# USB2XXX_1.net
KiCad netlist of a schematic drawn in Altium Designer
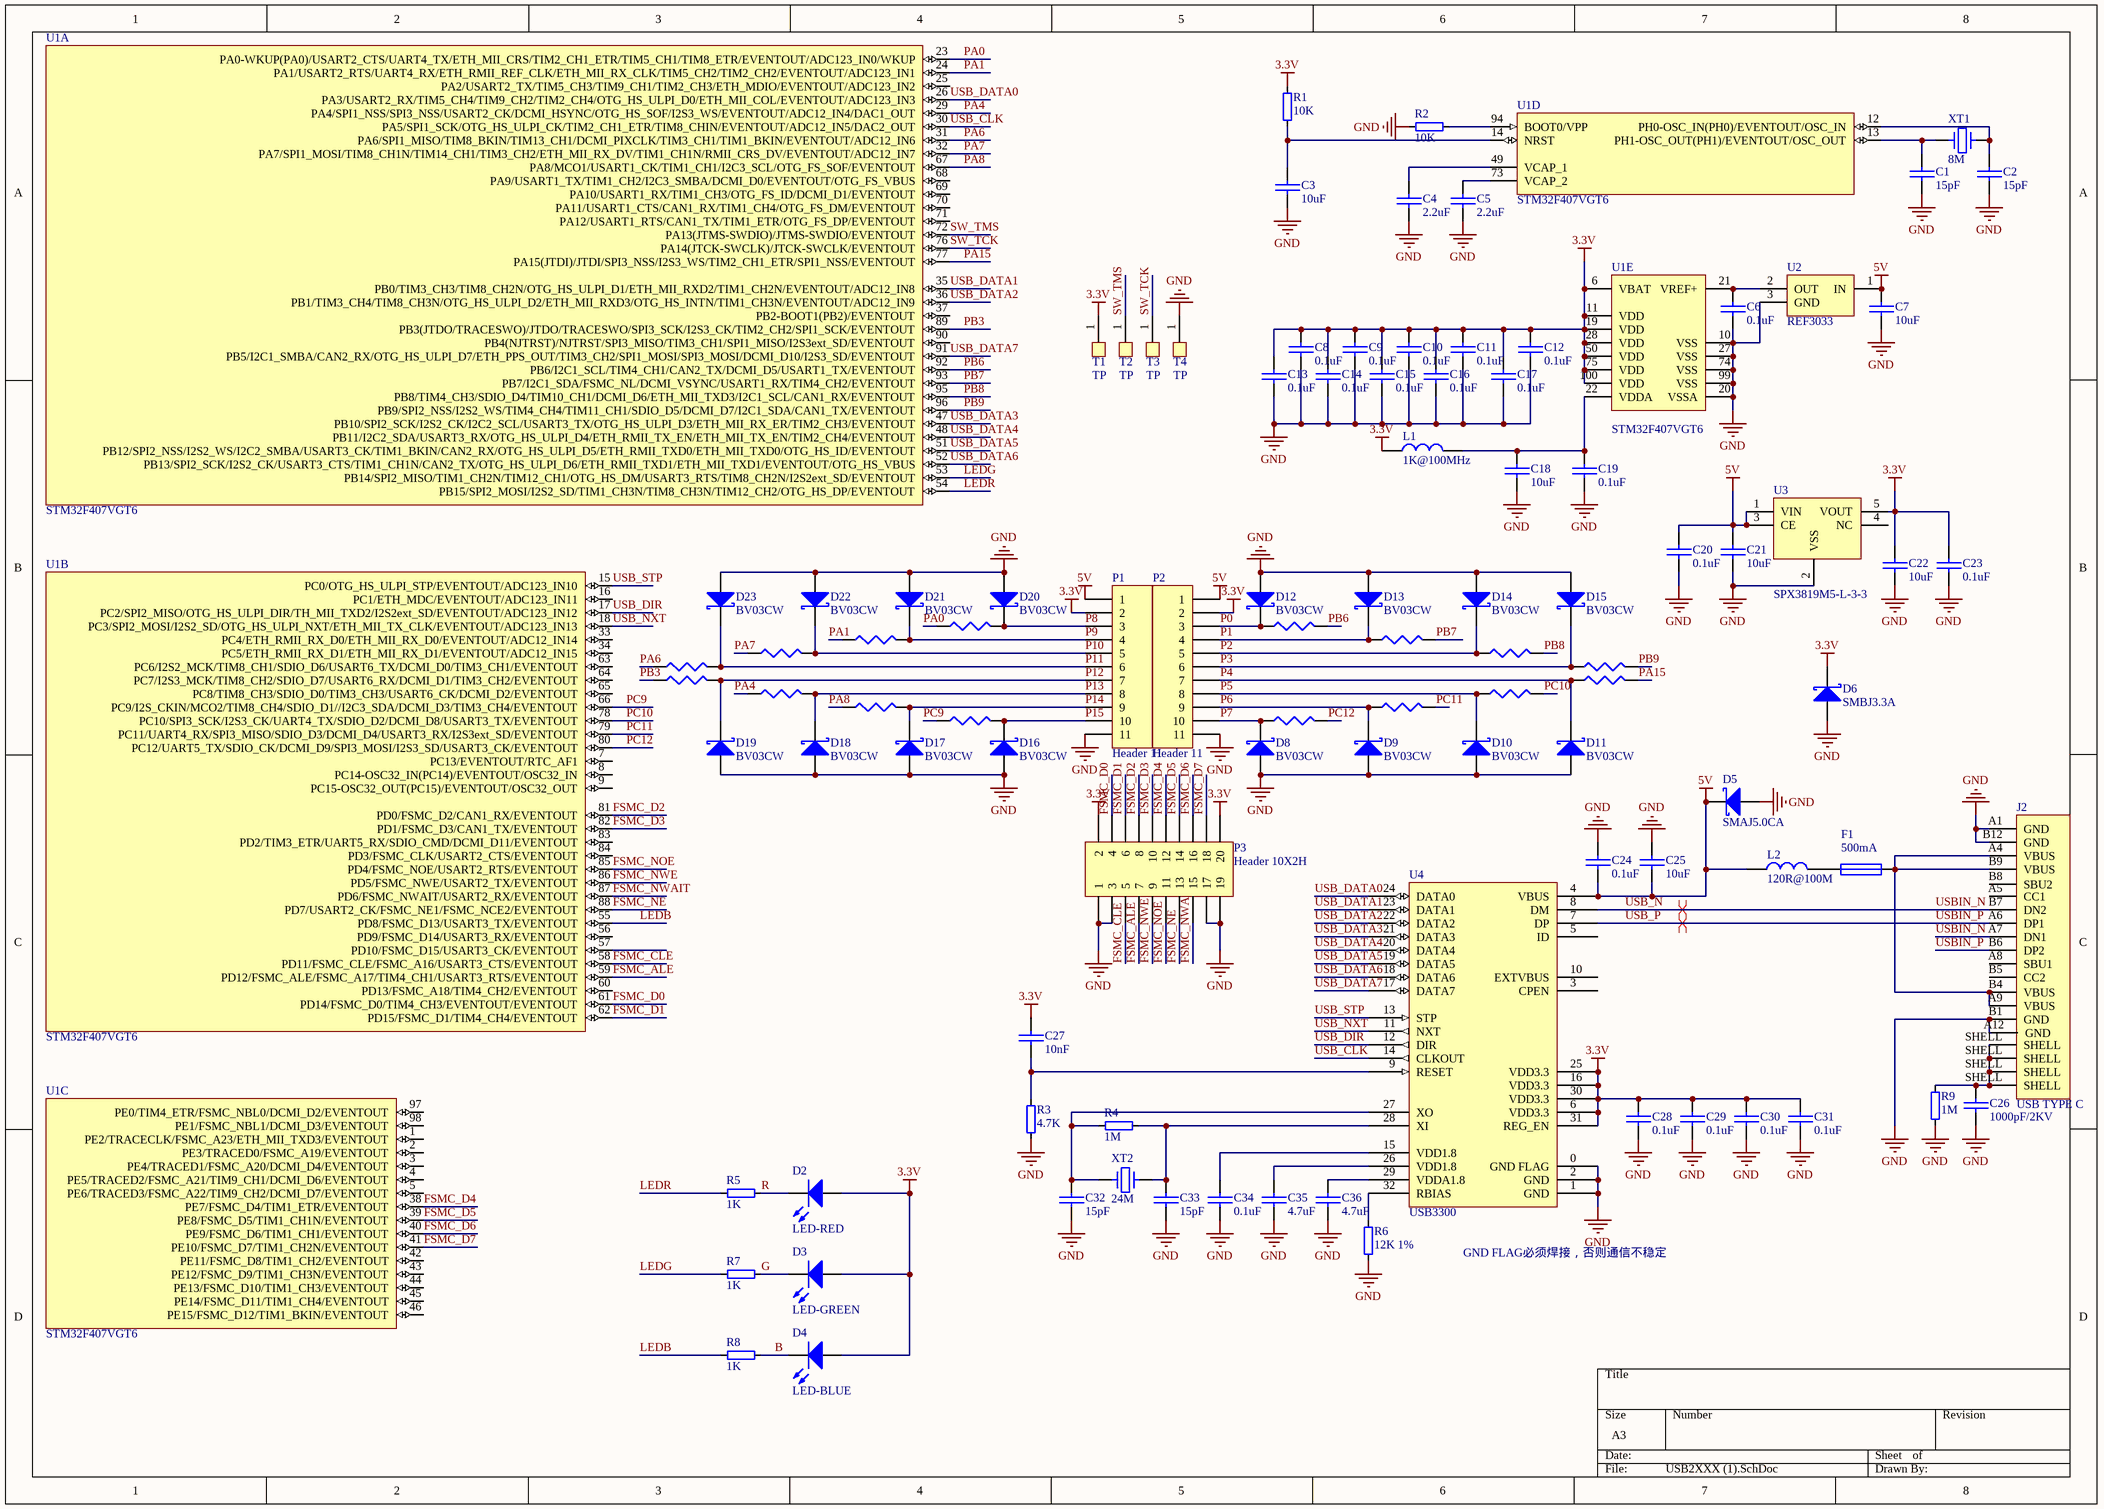
[diagram p0: USB2XXX (1).SchDoc]

(export (version "E")
  (design (tool "Eeschema 10.0.6"))
  (components
    (comp (ref "C1") (value "15pF") (footprint "C0402") (libsource (lib "Common Device") (part "Capacitor")))
    (comp (ref "C2") (value "15pF") (footprint "C0402") (libsource (lib "Common Device") (part "Capacitor")))
    (comp (ref "C3") (value "10uF") (footprint "C0603") (libsource (lib "Common Device") (part "Capacitor")))
    (comp (ref "C4") (value "2.2uF") (footprint "C0402") (libsource (lib "Common Device") (part "Capacitor")))
    (comp (ref "C5") (value "2.2uF") (footprint "C0402") (libsource (lib "Common Device") (part "Capacitor")))
    (comp (ref "C6") (value "0.1uF") (footprint "C0402") (libsource (lib "Common Device") (part "Capacitor")))
    (comp (ref "C7") (value "10uF") (footprint "C0603") (libsource (lib "Common Device") (part "Capacitor")))
    (comp (ref "C8") (value "0.1uF") (footprint "C0402") (libsource (lib "Common Device") (part "Capacitor")))
    (comp (ref "C9") (value "0.1uF") (footprint "C0402") (libsource (lib "Common Device") (part "Capacitor")))
    (comp (ref "C10")
      (value "0.1uF")
      (footprint "C0402")
      (libsource (lib "Common Device") (part "Capacitor"))
    )
    (comp (ref "C11")
      (value "0.1uF")
      (footprint "C0402")
      (libsource (lib "Common Device") (part "Capacitor"))
    )
    (comp (ref "C12")
      (value "0.1uF")
      (footprint "C0402")
      (libsource (lib "Common Device") (part "Capacitor"))
    )
    (comp (ref "C13")
      (value "0.1uF")
      (footprint "C0402")
      (libsource (lib "Common Device") (part "Capacitor"))
    )
    (comp (ref "C14")
      (value "0.1uF")
      (footprint "C0402")
      (libsource (lib "Common Device") (part "Capacitor"))
    )
    (comp (ref "C15")
      (value "0.1uF")
      (footprint "C0402")
      (libsource (lib "Common Device") (part "Capacitor"))
    )
    (comp (ref "C16")
      (value "0.1uF")
      (footprint "C0402")
      (libsource (lib "Common Device") (part "Capacitor"))
    )
    (comp (ref "C17")
      (value "0.1uF")
      (footprint "C0402")
      (libsource (lib "Common Device") (part "Capacitor"))
    )
    (comp (ref "C18") (value "10uF") (footprint "C0603") (libsource (lib "Common Device") (part "Capacitor")))
    (comp (ref "C19")
      (value "0.1uF")
      (footprint "C0402")
      (libsource (lib "Common Device") (part "Capacitor"))
    )
    (comp (ref "C20")
      (value "0.1uF")
      (footprint "C0402")
      (libsource (lib "Common Device") (part "Capacitor"))
    )
    (comp (ref "C21") (value "10uF") (footprint "C0603") (libsource (lib "Common Device") (part "Capacitor")))
    (comp (ref "C22") (value "10uF") (footprint "C0603") (libsource (lib "Common Device") (part "Capacitor")))
    (comp (ref "C23")
      (value "0.1uF")
      (footprint "Common Device:C0402")
      (libsource (lib "Common Device") (part "Capacitor"))
    )
    (comp (ref "C24")
      (value "0.1uF")
      (footprint "C0402")
      (libsource (lib "Common Device") (part "Capacitor"))
    )
    (comp (ref "C25") (value "10uF") (footprint "C0603") (libsource (lib "Common Device") (part "Capacitor")))
    (comp (ref "C26")
      (value "1000pF/2KV")
      (footprint "Common Device:C1206")
      (libsource (lib "Common Device") (part "Capacitor"))
    )
    (comp (ref "C27") (value "10nF") (footprint "C0402") (libsource (lib "Common Device") (part "Capacitor")))
    (comp (ref "C28")
      (value "0.1uF")
      (footprint "C0402")
      (libsource (lib "Common Device") (part "Capacitor"))
    )
    (comp (ref "C29")
      (value "0.1uF")
      (footprint "C0402")
      (libsource (lib "Common Device") (part "Capacitor"))
    )
    (comp (ref "C30")
      (value "0.1uF")
      (footprint "C0402")
      (libsource (lib "Common Device") (part "Capacitor"))
    )
    (comp (ref "C31")
      (value "0.1uF")
      (footprint "C0402")
      (libsource (lib "Common Device") (part "Capacitor"))
    )
    (comp (ref "C32") (value "15pF") (footprint "C0402") (libsource (lib "Common Device") (part "Capacitor")))
    (comp (ref "C33") (value "15pF") (footprint "C0402") (libsource (lib "Common Device") (part "Capacitor")))
    (comp (ref "C34")
      (value "0.1uF")
      (footprint "C0402")
      (libsource (lib "Common Device") (part "Capacitor"))
    )
    (comp (ref "C35")
      (value "4.7uF")
      (footprint "C0402")
      (libsource (lib "Common Device") (part "Capacitor"))
    )
    (comp (ref "C36")
      (value "4.7uF")
      (footprint "C0402")
      (libsource (lib "Common Device") (part "Capacitor"))
    )
    (comp (ref "D2") (value "LED-RED") (footprint "LED0603R") (libsource (lib "Common Device") (part "LED")))
    (comp (ref "D3")
      (value "LED-GREEN")
      (footprint "LED0603G")
      (libsource (lib "Common Device") (part "LED"))
    )
    (comp (ref "D4") (value "LED-BLUE") (footprint "LED0603B") (libsource (lib "Common Device") (part "LED")))
    (comp (ref "D5")
      (value "SMAJ5.0CA")
      (footprint "DO-214AC")
      (libsource (lib "Common Device") (part "Diode Schottky"))
    )
    (comp (ref "D6")
      (value "SMBJ3.3A")
      (footprint "DO-214AA")
      (libsource (lib "Common Device") (part "Diode Schottky"))
    )
    (comp (ref "D8")
      (value "BV03CW")
      (footprint "SOD323")
      (libsource (lib "Common Device") (part "Diode Schottky"))
    )
    (comp (ref "D9")
      (value "BV03CW")
      (footprint "SOD323")
      (libsource (lib "Common Device") (part "Diode Schottky"))
    )
    (comp (ref "D10")
      (value "BV03CW")
      (footprint "SOD323")
      (libsource (lib "Common Device") (part "Diode Schottky"))
    )
    (comp (ref "D11")
      (value "BV03CW")
      (footprint "SOD323")
      (libsource (lib "Common Device") (part "Diode Schottky"))
    )
    (comp (ref "D12")
      (value "BV03CW")
      (footprint "SOD323")
      (libsource (lib "Common Device") (part "Diode Schottky"))
    )
    (comp (ref "D13")
      (value "BV03CW")
      (footprint "SOD323")
      (libsource (lib "Common Device") (part "Diode Schottky"))
    )
    (comp (ref "D14")
      (value "BV03CW")
      (footprint "SOD323")
      (libsource (lib "Common Device") (part "Diode Schottky"))
    )
    (comp (ref "D15")
      (value "BV03CW")
      (footprint "SOD323")
      (libsource (lib "Common Device") (part "Diode Schottky"))
    )
    (comp (ref "D16")
      (value "BV03CW")
      (footprint "SOD323")
      (libsource (lib "Common Device") (part "Diode Schottky"))
    )
    (comp (ref "D17")
      (value "BV03CW")
      (footprint "SOD323")
      (libsource (lib "Common Device") (part "Diode Schottky"))
    )
    (comp (ref "D18")
      (value "BV03CW")
      (footprint "SOD323")
      (libsource (lib "Common Device") (part "Diode Schottky"))
    )
    (comp (ref "D19")
      (value "BV03CW")
      (footprint "SOD323")
      (libsource (lib "Common Device") (part "Diode Schottky"))
    )
    (comp (ref "D20")
      (value "BV03CW")
      (footprint "SOD323")
      (libsource (lib "Common Device") (part "Diode Schottky"))
    )
    (comp (ref "D21")
      (value "BV03CW")
      (footprint "SOD323")
      (libsource (lib "Common Device") (part "Diode Schottky"))
    )
    (comp (ref "D22")
      (value "BV03CW")
      (footprint "SOD323")
      (libsource (lib "Common Device") (part "Diode Schottky"))
    )
    (comp (ref "D23")
      (value "BV03CW")
      (footprint "SOD323")
      (libsource (lib "Common Device") (part "Diode Schottky"))
    )
    (comp (ref "F1")
      (value "500mA")
      (footprint "R0805")
      (description "FUSE")
      (libsource (lib "RCDQLY") (part "FUSE1"))
    )
    (comp (ref "J2")
      (value "USB TYPE C")
      (footprint "USB3.1_16P")
      (libsource (lib "Common Device") (part "USB_TYPE_C"))
    )
    (comp (ref "L1")
      (value "1K@100MHz")
      (footprint "R0603")
      (libsource (lib "Common Device") (part "Inductor"))
    )
    (comp (ref "L2")
      (value "120R@100M")
      (footprint "R0603")
      (libsource (lib "Common Device") (part "Inductor"))
    )
    (comp (ref "P1")
      (value "Header 11")
      (footprint "Common Headers:HDR1X11")
      (description "Header, 11-Pin")
      (fields (field (name "PUBLISHER") "Altium Limited"))
      (libsource (lib "Miscellaneous Connectors") (part "Header 11"))
    )
    (comp (ref "P2")
      (value "Header 11")
      (footprint "Common Headers:HDR1X11")
      (description "Header, 11-Pin")
      (fields (field (name "PUBLISHER") "Altium Limited"))
      (libsource (lib "") (part "Header 11_1"))
    )
    (comp (ref "P3")
      (value "Header 10X2H")
      (footprint "Common Headers:HDR2X10")
      (description "Header, 10-Pin, Dual row, Right Angle")
      (fields (field (name "PUBLISHER") "Altium Limited"))
      (libsource (lib "Miscellaneous Connectors") (part "Header 10X2H"))
    )
    (comp (ref "R1")
      (value "10K")
      (footprint "R0402")
      (description "resistor")
      (libsource (lib "RCDQLY") (part "R-10K"))
    )
    (comp (ref "R2")
      (value "10K")
      (footprint "R0402")
      (description "resistor")
      (libsource (lib "RCDQLY") (part "R-10K"))
    )
    (comp (ref "R3")
      (value "4.7K")
      (footprint "R0402")
      (description "resistor")
      (libsource (lib "RCDQLY") (part "R-10K"))
    )
    (comp (ref "R4")
      (value "1M")
      (footprint "R0402")
      (description "resistor")
      (libsource (lib "RCDQLY") (part "R-10K"))
    )
    (comp (ref "R5")
      (value "1K")
      (footprint "R0402")
      (description "resistor")
      (libsource (lib "RCDQLY") (part "R-10K"))
    )
    (comp (ref "R6")
      (value "12K 1%")
      (footprint "R0402")
      (description "resistor")
      (libsource (lib "RCDQLY") (part "R-10K"))
    )
    (comp (ref "R7")
      (value "1K")
      (footprint "R0402")
      (description "resistor")
      (libsource (lib "RCDQLY") (part "R-10K"))
    )
    (comp (ref "R8")
      (value "1K")
      (footprint "R0402")
      (description "resistor")
      (libsource (lib "RCDQLY") (part "R-10K"))
    )
    (comp (ref "R9")
      (value "1M")
      (footprint "R0402")
      (description "resistor")
      (libsource (lib "RCDQLY") (part "R-10K"))
    )
    (comp (ref "R10") (value "0R") (footprint "R0402") (libsource (lib "Common Device") (part "Resistance")))
    (comp (ref "R11") (value "0R") (footprint "R0402") (libsource (lib "Common Device") (part "Resistance")))
    (comp (ref "R12") (value "0R") (footprint "R0402") (libsource (lib "Common Device") (part "Resistance")))
    (comp (ref "R13") (value "0R") (footprint "R0402") (libsource (lib "Common Device") (part "Resistance")))
    (comp (ref "R14") (value "0R") (footprint "R0402") (libsource (lib "Common Device") (part "Resistance")))
    (comp (ref "R15") (value "0R") (footprint "R0402") (libsource (lib "Common Device") (part "Resistance")))
    (comp (ref "R16") (value "0R") (footprint "R0402") (libsource (lib "Common Device") (part "Resistance")))
    (comp (ref "R17") (value "0R") (footprint "R0402") (libsource (lib "Common Device") (part "Resistance")))
    (comp (ref "R18") (value "0R") (footprint "R0402") (libsource (lib "Common Device") (part "Resistance")))
    (comp (ref "R19") (value "0R") (footprint "R0402") (libsource (lib "Common Device") (part "Resistance")))
    (comp (ref "R20") (value "0R") (footprint "R0402") (libsource (lib "Common Device") (part "Resistance")))
    (comp (ref "R21") (value "0R") (footprint "R0402") (libsource (lib "Common Device") (part "Resistance")))
    (comp (ref "R22") (value "0R") (footprint "R0402") (libsource (lib "Common Device") (part "Resistance")))
    (comp (ref "R23") (value "0R") (footprint "R0402") (libsource (lib "Common Device") (part "Resistance")))
    (comp (ref "R24") (value "0R") (footprint "R0402") (libsource (lib "Common Device") (part "Resistance")))
    (comp (ref "R25") (value "0R") (footprint "R0402") (libsource (lib "Common Device") (part "Resistance")))
    (comp (ref "T1") (value "TP") (footprint "TP15") (libsource (lib "Common Device") (part "TP")))
    (comp (ref "T2") (value "TP") (footprint "TP15") (libsource (lib "Common Device") (part "TP")))
    (comp (ref "T3") (value "TP") (footprint "TP15") (libsource (lib "Common Device") (part "TP")))
    (comp (ref "T4") (value "TP") (footprint "TP15") (libsource (lib "Common Device") (part "TP")))
    (comp (ref "U1")
      (value "STM32F407VGT6")
      (footprint "TQFP-100")
      (libsource (lib "STMicroelectronics STM32 F4") (part "STM32F407VGT6"))
    )
    (comp (ref "U2")
      (value "REF3033")
      (footprint "SOT-23")
      (libsource (lib "Common Device") (part "REF33XX"))
    )
    (comp (ref "U3")
      (value "SPX3819M5-L-3-3")
      (footprint "Common Device:SOT23-5")
      (libsource (lib "Common Power") (part "ME6211"))
    )
    (comp (ref "U4")
      (value "USB3300")
      (footprint "QFN50P500X500X100-32N")
      (libsource (lib "IC") (part "USB3300"))
    )
    (comp (ref "XT1")
      (value "8M")
      (footprint "CRYSTAL-SMD-5032")
      (description "晶振")
      (libsource (lib "RCDQLY") (part "XT"))
    )
    (comp (ref "XT2")
      (value "24M")
      (footprint "CRYSTAL-SMD-5032")
      (description "晶振")
      (libsource (lib "RCDQLY") (part "XT"))
    )
  )
  (nets
    (net (code "1") (name "/B") (class "Default")
      (node (ref "D4") (pin "2") (pinfunction "K_2") (pintype "passive"))
      (node (ref "R8") (pin "2") (pinfunction "2_2") (pintype "passive"))
    )
    (net (code "2") (name "/FSMC_ALE") (class "Default")
      (node (ref "P3") (pin "7") (pinfunction "7_7") (pintype "passive"))
      (node (ref "U1") (pin "59") (pinfunction "PD12/FSMC_ALE/FSMC_A17/TIM4_CH1/USART3_RTS/EVENTOUT_59") (pintype "bidirectional"))
    )
    (net (code "3") (name "/FSMC_CLE") (class "Default")
      (node (ref "P3") (pin "5") (pinfunction "5_5") (pintype "passive"))
      (node (ref "U1") (pin "58") (pinfunction "PD11/FSMC_CLE/FSMC_A16/USART3_CTS/EVENTOUT_58") (pintype "bidirectional"))
    )
    (net (code "4") (name "/FSMC_D0") (class "Default")
      (node (ref "P3") (pin "4") (pinfunction "4_4") (pintype "passive"))
      (node (ref "U1") (pin "61") (pinfunction "PD14/FSMC_D0/TIM4_CH3/EVENTOUT/EVENTOUT_61") (pintype "bidirectional"))
    )
    (net (code "5") (name "/FSMC_D1") (class "Default")
      (node (ref "P3") (pin "6") (pinfunction "6_6") (pintype "passive"))
      (node (ref "U1") (pin "62") (pinfunction "PD15/FSMC_D1/TIM4_CH4/EVENTOUT_62") (pintype "bidirectional"))
    )
    (net (code "6") (name "/FSMC_D2") (class "Default")
      (node (ref "P3") (pin "8") (pinfunction "8_8") (pintype "passive"))
      (node (ref "U1") (pin "81") (pinfunction "PD0/FSMC_D2/CAN1_RX/EVENTOUT_81") (pintype "bidirectional"))
    )
    (net (code "7") (name "/FSMC_D3") (class "Default")
      (node (ref "P3") (pin "10") (pinfunction "10_10") (pintype "passive"))
      (node (ref "U1") (pin "82") (pinfunction "PD1/FSMC_D3/CAN1_TX/EVENTOUT_82") (pintype "bidirectional"))
    )
    (net (code "8") (name "/FSMC_D4") (class "Default")
      (node (ref "P3") (pin "12") (pinfunction "12_12") (pintype "passive"))
      (node (ref "U1") (pin "38") (pinfunction "PE7/FSMC_D4/TIM1_ETR/EVENTOUT_38") (pintype "bidirectional"))
    )
    (net (code "9") (name "/FSMC_D5") (class "Default")
      (node (ref "P3") (pin "14") (pinfunction "14_14") (pintype "passive"))
      (node (ref "U1") (pin "39") (pinfunction "PE8/FSMC_D5/TIM1_CH1N/EVENTOUT_39") (pintype "bidirectional"))
    )
    (net (code "10") (name "/FSMC_D6") (class "Default")
      (node (ref "P3") (pin "16") (pinfunction "16_16") (pintype "passive"))
      (node (ref "U1") (pin "40") (pinfunction "PE9/FSMC_D6/TIM1_CH1/EVENTOUT_40") (pintype "bidirectional"))
    )
    (net (code "11") (name "/FSMC_D7") (class "Default")
      (node (ref "P3") (pin "18") (pinfunction "18_18") (pintype "passive"))
      (node (ref "U1") (pin "41") (pinfunction "PE10/FSMC_D7/TIM1_CH2N/EVENTOUT_41") (pintype "bidirectional"))
    )
    (net (code "12") (name "/FSMC_NE") (class "Default")
      (node (ref "P3") (pin "13") (pinfunction "13_13") (pintype "passive"))
      (node (ref "U1") (pin "88") (pinfunction "PD7/USART2_CK/FSMC_NE1/FSMC_NCE2/EVENTOUT_88") (pintype "bidirectional"))
    )
    (net (code "13") (name "/FSMC_NOE") (class "Default")
      (node (ref "P3") (pin "11") (pinfunction "11_11") (pintype "passive"))
      (node (ref "U1") (pin "85") (pinfunction "PD4/FSMC_NOE/USART2_RTS/EVENTOUT_85") (pintype "bidirectional"))
    )
    (net (code "14") (name "/FSMC_NWAIT") (class "Default")
      (node (ref "P3") (pin "15") (pinfunction "15_15") (pintype "passive"))
      (node (ref "U1") (pin "87") (pinfunction "PD6/FSMC_NWAIT/USART2_RX/EVENTOUT_87") (pintype "bidirectional"))
    )
    (net (code "15") (name "/FSMC_NWE") (class "Default")
      (node (ref "P3") (pin "9") (pinfunction "9_9") (pintype "passive"))
      (node (ref "U1") (pin "86") (pinfunction "PD5/FSMC_NWE/USART2_TX/EVENTOUT_86") (pintype "bidirectional"))
    )
    (net (code "16") (name "/G") (class "Default")
      (node (ref "D3") (pin "2") (pinfunction "K_2") (pintype "passive"))
      (node (ref "R7") (pin "2") (pinfunction "2_2") (pintype "passive"))
    )
    (net (code "17") (name "/LEDB") (class "Default")
      (node (ref "R8") (pin "1") (pinfunction "1_1") (pintype "passive"))
      (node (ref "U1") (pin "55") (pinfunction "PD8/FSMC_D13/USART3_TX/EVENTOUT_55") (pintype "bidirectional"))
    )
    (net (code "18") (name "/LEDG") (class "Default")
      (node (ref "R7") (pin "1") (pinfunction "1_1") (pintype "passive"))
      (node (ref "U1") (pin "53") (pinfunction "PB14/SPI2_MISO/TIM1_CH2N/TIM12_CH1/OTG_HS_DM/USART3_RTS/TIM8_CH2N/I2S2ext_SD/EVENTOUT_53") (pintype "bidirectional"))
    )
    (net (code "19") (name "/LEDR") (class "Default")
      (node (ref "R5") (pin "1") (pinfunction "1_1") (pintype "passive"))
      (node (ref "U1") (pin "54") (pinfunction "PB15/SPI2_MOSI/I2S2_SD/TIM1_CH3N/TIM8_CH3N/TIM12_CH2/OTG_HS_DP/EVENTOUT_54") (pintype "bidirectional"))
    )
    (net (code "20") (name "/P0") (class "Default")
      (node (ref "D12") (pin "2") (pinfunction "K_2") (pintype "passive"))
      (node (ref "P2") (pin "3") (pinfunction "3_3") (pintype "passive"))
      (node (ref "R18") (pin "1") (pinfunction "1_1") (pintype "passive"))
    )
    (net (code "21") (name "/P1") (class "Default")
      (node (ref "D13") (pin "2") (pinfunction "K_2") (pintype "passive"))
      (node (ref "P2") (pin "4") (pinfunction "4_4") (pintype "passive"))
      (node (ref "R19") (pin "1") (pinfunction "1_1") (pintype "passive"))
    )
    (net (code "22") (name "/P2") (class "Default")
      (node (ref "D14") (pin "2") (pinfunction "K_2") (pintype "passive"))
      (node (ref "P2") (pin "5") (pinfunction "5_5") (pintype "passive"))
      (node (ref "R20") (pin "1") (pinfunction "1_1") (pintype "passive"))
    )
    (net (code "23") (name "/P3") (class "Default")
      (node (ref "D15") (pin "2") (pinfunction "K_2") (pintype "passive"))
      (node (ref "P2") (pin "6") (pinfunction "6_6") (pintype "passive"))
      (node (ref "R21") (pin "1") (pinfunction "1_1") (pintype "passive"))
    )
    (net (code "24") (name "/P4") (class "Default")
      (node (ref "D11") (pin "2") (pinfunction "K_2") (pintype "passive"))
      (node (ref "P2") (pin "7") (pinfunction "7_7") (pintype "passive"))
      (node (ref "R22") (pin "1") (pinfunction "1_1") (pintype "passive"))
    )
    (net (code "25") (name "/P5") (class "Default")
      (node (ref "D10") (pin "2") (pinfunction "K_2") (pintype "passive"))
      (node (ref "P2") (pin "8") (pinfunction "8_8") (pintype "passive"))
      (node (ref "R23") (pin "1") (pinfunction "1_1") (pintype "passive"))
    )
    (net (code "26") (name "/P6") (class "Default")
      (node (ref "D9") (pin "2") (pinfunction "K_2") (pintype "passive"))
      (node (ref "P2") (pin "9") (pinfunction "9_9") (pintype "passive"))
      (node (ref "R24") (pin "1") (pinfunction "1_1") (pintype "passive"))
    )
    (net (code "27") (name "/P7") (class "Default")
      (node (ref "D8") (pin "2") (pinfunction "K_2") (pintype "passive"))
      (node (ref "P2") (pin "10") (pinfunction "10_10") (pintype "passive"))
      (node (ref "R25") (pin "1") (pinfunction "1_1") (pintype "passive"))
    )
    (net (code "28") (name "/P8") (class "Default")
      (node (ref "D20") (pin "2") (pinfunction "K_2") (pintype "passive"))
      (node (ref "P1") (pin "3") (pinfunction "3_3") (pintype "passive"))
      (node (ref "R10") (pin "2") (pinfunction "2_2") (pintype "passive"))
    )
    (net (code "29") (name "/P9") (class "Default")
      (node (ref "D21") (pin "2") (pinfunction "K_2") (pintype "passive"))
      (node (ref "P1") (pin "4") (pinfunction "4_4") (pintype "passive"))
      (node (ref "R11") (pin "2") (pinfunction "2_2") (pintype "passive"))
    )
    (net (code "30") (name "/P10") (class "Default")
      (node (ref "D22") (pin "2") (pinfunction "K_2") (pintype "passive"))
      (node (ref "P1") (pin "5") (pinfunction "5_5") (pintype "passive"))
      (node (ref "R12") (pin "2") (pinfunction "2_2") (pintype "passive"))
    )
    (net (code "31") (name "/P11") (class "Default")
      (node (ref "D23") (pin "2") (pinfunction "K_2") (pintype "passive"))
      (node (ref "P1") (pin "6") (pinfunction "6_6") (pintype "passive"))
      (node (ref "R13") (pin "2") (pinfunction "2_2") (pintype "passive"))
    )
    (net (code "32") (name "/P12") (class "Default")
      (node (ref "D19") (pin "2") (pinfunction "K_2") (pintype "passive"))
      (node (ref "P1") (pin "7") (pinfunction "7_7") (pintype "passive"))
      (node (ref "R14") (pin "2") (pinfunction "2_2") (pintype "passive"))
    )
    (net (code "33") (name "/P13") (class "Default")
      (node (ref "D18") (pin "2") (pinfunction "K_2") (pintype "passive"))
      (node (ref "P1") (pin "8") (pinfunction "8_8") (pintype "passive"))
      (node (ref "R15") (pin "2") (pinfunction "2_2") (pintype "passive"))
    )
    (net (code "34") (name "/P14") (class "Default")
      (node (ref "D17") (pin "2") (pinfunction "K_2") (pintype "passive"))
      (node (ref "P1") (pin "9") (pinfunction "9_9") (pintype "passive"))
      (node (ref "R16") (pin "2") (pinfunction "2_2") (pintype "passive"))
    )
    (net (code "35") (name "/P15") (class "Default")
      (node (ref "D16") (pin "2") (pinfunction "K_2") (pintype "passive"))
      (node (ref "P1") (pin "10") (pinfunction "10_10") (pintype "passive"))
      (node (ref "R17") (pin "2") (pinfunction "2_2") (pintype "passive"))
    )
    (net (code "36") (name "/PA0") (class "Default")
      (node (ref "R10") (pin "1") (pinfunction "1_1") (pintype "passive"))
      (node (ref "U1") (pin "23") (pinfunction "PA0-WKUP(PA0)/USART2_CTS/UART4_TX/ETH_MII_CRS/TIM2_CH1_ETR/TIM5_CH1/TIM8_ETR/EVENTOUT/ADC123_IN0/WKUP_23") (pintype "bidirectional"))
    )
    (net (code "37") (name "/PA1") (class "Default")
      (node (ref "R11") (pin "1") (pinfunction "1_1") (pintype "passive"))
      (node (ref "U1") (pin "24") (pinfunction "PA1/USART2_RTS/UART4_RX/ETH_RMII_REF_CLK/ETH_MII_RX_CLK/TIM5_CH2/TIM2_CH2/EVENTOUT/ADC123_IN1_24") (pintype "bidirectional"))
    )
    (net (code "38") (name "/PA4") (class "Default")
      (node (ref "R15") (pin "1") (pinfunction "1_1") (pintype "passive"))
      (node (ref "U1") (pin "29") (pinfunction "PA4/SPI1_NSS/SPI3_NSS/USART2_CK/DCMI_HSYNC/OTG_HS_SOF/I2S3_WS/EVENTOUT/ADC12_IN4/DAC1_OUT_29") (pintype "bidirectional"))
    )
    (net (code "39") (name "/PA6") (class "Default")
      (node (ref "R13") (pin "1") (pinfunction "1_1") (pintype "passive"))
      (node (ref "U1") (pin "31") (pinfunction "PA6/SPI1_MISO/TIM8_BKIN/TIM13_CH1/DCMI_PIXCLK/TIM3_CH1/TIM1_BKIN/EVENTOUT/ADC12_IN6_31") (pintype "bidirectional"))
    )
    (net (code "40") (name "/PA7") (class "Default")
      (node (ref "R12") (pin "1") (pinfunction "1_1") (pintype "passive"))
      (node (ref "U1") (pin "32") (pinfunction "PA7/SPI1_MOSI/TIM8_CH1N/TIM14_CH1/TIM3_CH2/ETH_MII_RX_DV/TIM1_CH1N/RMII_CRS_DV/EVENTOUT/ADC12_IN7_32") (pintype "bidirectional"))
    )
    (net (code "41") (name "/PA8") (class "Default")
      (node (ref "R16") (pin "1") (pinfunction "1_1") (pintype "passive"))
      (node (ref "U1") (pin "67") (pinfunction "PA8/MCO1/USART1_CK/TIM1_CH1/I2C3_SCL/OTG_FS_SOF/EVENTOUT_67") (pintype "bidirectional"))
    )
    (net (code "42") (name "/PA15") (class "Default")
      (node (ref "R22") (pin "2") (pinfunction "2_2") (pintype "passive"))
      (node (ref "U1") (pin "77") (pinfunction "PA15(JTDI)/JTDI/SPI3_NSS/I2S3_WS/TIM2_CH1_ETR/SPI1_NSS/EVENTOUT_77") (pintype "bidirectional"))
    )
    (net (code "43") (name "/PB3") (class "Default")
      (node (ref "R14") (pin "1") (pinfunction "1_1") (pintype "passive"))
      (node (ref "U1") (pin "89") (pinfunction "PB3(JTDO/TRACESWO)/JTDO/TRACESWO/SPI3_SCK/I2S3_CK/TIM2_CH2/SPI1_SCK/EVENTOUT_89") (pintype "bidirectional"))
    )
    (net (code "44") (name "/PB6") (class "Default")
      (node (ref "R18") (pin "2") (pinfunction "2_2") (pintype "passive"))
      (node (ref "U1") (pin "92") (pinfunction "PB6/I2C1_SCL/TIM4_CH1/CAN2_TX/DCMI_D5/USART1_TX/EVENTOUT_92") (pintype "bidirectional"))
    )
    (net (code "45") (name "/PB7") (class "Default")
      (node (ref "R19") (pin "2") (pinfunction "2_2") (pintype "passive"))
      (node (ref "U1") (pin "93") (pinfunction "PB7/I2C1_SDA/FSMC_NL/DCMI_VSYNC/USART1_RX/TIM4_CH2/EVENTOUT_93") (pintype "bidirectional"))
    )
    (net (code "46") (name "/PB8") (class "Default")
      (node (ref "R20") (pin "2") (pinfunction "2_2") (pintype "passive"))
      (node (ref "U1") (pin "95") (pinfunction "PB8/TIM4_CH3/SDIO_D4/TIM10_CH1/DCMI_D6/ETH_MII_TXD3/I2C1_SCL/CAN1_RX/EVENTOUT_95") (pintype "bidirectional"))
    )
    (net (code "47") (name "/PB9") (class "Default")
      (node (ref "R21") (pin "2") (pinfunction "2_2") (pintype "passive"))
      (node (ref "U1") (pin "96") (pinfunction "PB9/SPI2_NSS/I2S2_WS/TIM4_CH4/TIM11_CH1/SDIO_D5/DCMI_D7/I2C1_SDA/CAN1_TX/EVENTOUT_96") (pintype "bidirectional"))
    )
    (net (code "48") (name "/PC9") (class "Default")
      (node (ref "R17") (pin "1") (pinfunction "1_1") (pintype "passive"))
      (node (ref "U1") (pin "66") (pinfunction "PC9/I2S_CKIN/MCO2/TIM8_CH4/SDIO_D1//I2C3_SDA/DCMI_D3/TIM3_CH4/EVENTOUT_66") (pintype "bidirectional"))
    )
    (net (code "49") (name "/PC10") (class "Default")
      (node (ref "R23") (pin "2") (pinfunction "2_2") (pintype "passive"))
      (node (ref "U1") (pin "78") (pinfunction "PC10/SPI3_SCK/I2S3_CK/UART4_TX/SDIO_D2/DCMI_D8/USART3_TX/EVENTOUT_78") (pintype "bidirectional"))
    )
    (net (code "50") (name "/PC11") (class "Default")
      (node (ref "R24") (pin "2") (pinfunction "2_2") (pintype "passive"))
      (node (ref "U1") (pin "79") (pinfunction "PC11/UART4_RX/SPI3_MISO/SDIO_D3/DCMI_D4/USART3_RX/I2S3ext_SD/EVENTOUT_79") (pintype "bidirectional"))
    )
    (net (code "51") (name "/PC12") (class "Default")
      (node (ref "R25") (pin "2") (pinfunction "2_2") (pintype "passive"))
      (node (ref "U1") (pin "80") (pinfunction "PC12/UART5_TX/SDIO_CK/DCMI_D9/SPI3_MOSI/I2S3_SD/USART3_CK/EVENTOUT_80") (pintype "bidirectional"))
    )
    (net (code "52") (name "/R") (class "Default")
      (node (ref "D2") (pin "2") (pinfunction "K_2") (pintype "passive"))
      (node (ref "R5") (pin "2") (pinfunction "2_2") (pintype "passive"))
    )
    (net (code "53") (name "/SW_TCK") (class "Default")
      (node (ref "T3") (pin "1") (pintype "power_in"))
      (node (ref "U1") (pin "76") (pinfunction "PA14(JTCK-SWCLK)/JTCK-SWCLK/EVENTOUT_76") (pintype "bidirectional"))
    )
    (net (code "54") (name "/SW_TMS") (class "Default")
      (node (ref "T2") (pin "1") (pintype "power_in"))
      (node (ref "U1") (pin "72") (pinfunction "PA13(JTMS-SWDIO)/JTMS-SWDIO/EVENTOUT_72") (pintype "bidirectional"))
    )
    (net (code "55") (name "/USBIN_N") (class "Default")
      (node (ref "J2") (pin "A7") (pinfunction "DN1_A7") (pintype "passive"))
      (node (ref "J2") (pin "B7") (pinfunction "DN2_B7") (pintype "passive"))
      (node (ref "U4") (pin "8") (pinfunction "DM_8") (pintype "passive"))
    )
    (net (code "56") (name "/USBIN_P") (class "Default")
      (node (ref "J2") (pin "A6") (pinfunction "DP1_A6") (pintype "passive"))
      (node (ref "J2") (pin "B6") (pinfunction "DP2_B6") (pintype "passive"))
      (node (ref "U4") (pin "7") (pinfunction "DP_7") (pintype "passive"))
    )
    (net (code "57") (name "/USB_CLK") (class "Default")
      (node (ref "U1") (pin "30") (pinfunction "PA5/SPI1_SCK/OTG_HS_ULPI_CK/TIM2_CH1_ETR/TIM8_CHIN/EVENTOUT/ADC12_IN5/DAC2_OUT_30") (pintype "bidirectional"))
      (node (ref "U4") (pin "14") (pinfunction "CLKOUT_14") (pintype "output"))
    )
    (net (code "58") (name "/USB_DATA0") (class "Default")
      (node (ref "U1") (pin "26") (pinfunction "PA3/USART2_RX/TIM5_CH4/TIM9_CH2/TIM2_CH4/OTG_HS_ULPI_D0/ETH_MII_COL/EVENTOUT/ADC123_IN3_26") (pintype "bidirectional"))
      (node (ref "U4") (pin "24") (pinfunction "DATA0_24") (pintype "bidirectional"))
    )
    (net (code "59") (name "/USB_DATA1") (class "Default")
      (node (ref "U1") (pin "35") (pinfunction "PB0/TIM3_CH3/TIM8_CH2N/OTG_HS_ULPI_D1/ETH_MII_RXD2/TIM1_CH2N/EVENTOUT/ADC12_IN8_35") (pintype "bidirectional"))
      (node (ref "U4") (pin "23") (pinfunction "DATA1_23") (pintype "bidirectional"))
    )
    (net (code "60") (name "/USB_DATA2") (class "Default")
      (node (ref "U1") (pin "36") (pinfunction "PB1/TIM3_CH4/TIM8_CH3N/OTG_HS_ULPI_D2/ETH_MII_RXD3/OTG_HS_INTN/TIM1_CH3N/EVENTOUT/ADC12_IN9_36") (pintype "bidirectional"))
      (node (ref "U4") (pin "22") (pinfunction "DATA2_22") (pintype "bidirectional"))
    )
    (net (code "61") (name "/USB_DATA3") (class "Default")
      (node (ref "U1") (pin "47") (pinfunction "PB10/SPI2_SCK/I2S2_CK/I2C2_SCL/USART3_TX/OTG_HS_ULPI_D3/ETH_MII_RX_ER/TIM2_CH3/EVENTOUT_47") (pintype "bidirectional"))
      (node (ref "U4") (pin "21") (pinfunction "DATA3_21") (pintype "bidirectional"))
    )
    (net (code "62") (name "/USB_DATA4") (class "Default")
      (node (ref "U1") (pin "48") (pinfunction "PB11/I2C2_SDA/USART3_RX/OTG_HS_ULPI_D4/ETH_RMII_TX_EN/ETH_MII_TX_EN/TIM2_CH4/EVENTOUT_48") (pintype "bidirectional"))
      (node (ref "U4") (pin "20") (pinfunction "DATA4_20") (pintype "bidirectional"))
    )
    (net (code "63") (name "/USB_DATA5") (class "Default")
      (node (ref "U1") (pin "51") (pinfunction "PB12/SPI2_NSS/I2S2_WS/I2C2_SMBA/USART3_CK/TIM1_BKIN/CAN2_RX/OTG_HS_ULPI_D5/ETH_RMII_TXD0/ETH_MII_TXD0/OTG_HS_ID/EVENTOUT_51") (pintype "bidirectional"))
      (node (ref "U4") (pin "19") (pinfunction "DATA5_19") (pintype "bidirectional"))
    )
    (net (code "64") (name "/USB_DATA6") (class "Default")
      (node (ref "U1") (pin "52") (pinfunction "PB13/SPI2_SCK/I2S2_CK/USART3_CTS/TIM1_CH1N/CAN2_TX/OTG_HS_ULPI_D6/ETH_RMII_TXD1/ETH_MII_TXD1/EVENTOUT/OTG_HS_VBUS_52") (pintype "bidirectional"))
      (node (ref "U4") (pin "18") (pinfunction "DATA6_18") (pintype "bidirectional"))
    )
    (net (code "65") (name "/USB_DATA7") (class "Default")
      (node (ref "U1") (pin "91") (pinfunction "PB5/I2C1_SMBA/CAN2_RX/OTG_HS_ULPI_D7/ETH_PPS_OUT/TIM3_CH2/SPI1_MOSI/SPI3_MOSI/DCMI_D10/I2S3_SD/EVENTOUT_91") (pintype "bidirectional"))
      (node (ref "U4") (pin "17") (pinfunction "DATA7_17") (pintype "bidirectional"))
    )
    (net (code "66") (name "/USB_DIR") (class "Default")
      (node (ref "U1") (pin "17") (pinfunction "PC2/SPI2_MISO/OTG_HS_ULPI_DIR/TH_MII_TXD2/I2S2ext_SD/EVENTOUT/ADC123_IN12_17") (pintype "bidirectional"))
      (node (ref "U4") (pin "12") (pinfunction "DIR_12") (pintype "output"))
    )
    (net (code "67") (name "/USB_NXT") (class "Default")
      (node (ref "U1") (pin "18") (pinfunction "PC3/SPI2_MOSI/I2S2_SD/OTG_HS_ULPI_NXT/ETH_MII_TX_CLK/EVENTOUT/ADC123_IN13_18") (pintype "bidirectional"))
      (node (ref "U4") (pin "11") (pinfunction "NXT_11") (pintype "output"))
    )
    (net (code "68") (name "/USB_STP") (class "Default")
      (node (ref "U1") (pin "15") (pinfunction "PC0/OTG_HS_ULPI_STP/EVENTOUT/ADC123_IN10_15") (pintype "bidirectional"))
      (node (ref "U4") (pin "13") (pinfunction "STP_13") (pintype "input"))
    )
    (net (code "69") (name "3.3V") (class "Default")
      (node (ref "C10") (pin "2") (pinfunction "2_2") (pintype "passive"))
      (node (ref "C11") (pin "2") (pinfunction "2_2") (pintype "passive"))
      (node (ref "C12") (pin "2") (pinfunction "2_2") (pintype "passive"))
      (node (ref "C13") (pin "2") (pinfunction "2_2") (pintype "passive"))
      (node (ref "C14") (pin "2") (pinfunction "2_2") (pintype "passive"))
      (node (ref "C15") (pin "2") (pinfunction "2_2") (pintype "passive"))
      (node (ref "C16") (pin "2") (pinfunction "2_2") (pintype "passive"))
      (node (ref "C17") (pin "2") (pinfunction "2_2") (pintype "passive"))
      (node (ref "C22") (pin "2") (pinfunction "2_2") (pintype "passive"))
      (node (ref "C23") (pin "2") (pinfunction "2_2") (pintype "passive"))
      (node (ref "C27") (pin "2") (pinfunction "2_2") (pintype "passive"))
      (node (ref "C28") (pin "2") (pinfunction "2_2") (pintype "passive"))
      (node (ref "C29") (pin "2") (pinfunction "2_2") (pintype "passive"))
      (node (ref "C30") (pin "2") (pinfunction "2_2") (pintype "passive"))
      (node (ref "C31") (pin "2") (pinfunction "2_2") (pintype "passive"))
      (node (ref "C8") (pin "2") (pinfunction "2_2") (pintype "passive"))
      (node (ref "C9") (pin "2") (pinfunction "2_2") (pintype "passive"))
      (node (ref "D2") (pin "1") (pinfunction "A_1") (pintype "passive"))
      (node (ref "D3") (pin "1") (pinfunction "A_1") (pintype "passive"))
      (node (ref "D4") (pin "1") (pinfunction "A_1") (pintype "passive"))
      (node (ref "D6") (pin "2") (pinfunction "K_2") (pintype "passive"))
      (node (ref "L1") (pin "1") (pinfunction "1_1") (pintype "passive"))
      (node (ref "P1") (pin "2") (pinfunction "2_2") (pintype "passive"))
      (node (ref "P2") (pin "2") (pinfunction "2_2") (pintype "passive"))
      (node (ref "P3") (pin "2") (pinfunction "2_2") (pintype "passive"))
      (node (ref "P3") (pin "20") (pinfunction "20_20") (pintype "passive"))
      (node (ref "R1") (pin "2") (pinfunction "2_2") (pintype "passive"))
      (node (ref "T1") (pin "1") (pintype "power_in"))
      (node (ref "U1") (pin "100") (pinfunction "VDD_100") (pintype "power_in"))
      (node (ref "U1") (pin "11") (pinfunction "VDD_11") (pintype "power_in"))
      (node (ref "U1") (pin "19") (pinfunction "VDD_19") (pintype "power_in"))
      (node (ref "U1") (pin "28") (pinfunction "VDD_28") (pintype "power_in"))
      (node (ref "U1") (pin "50") (pinfunction "VDD_50") (pintype "power_in"))
      (node (ref "U1") (pin "6") (pinfunction "VBAT_6") (pintype "power_in"))
      (node (ref "U1") (pin "75") (pinfunction "VDD_75") (pintype "power_in"))
      (node (ref "U3") (pin "5") (pinfunction "VOUT_5") (pintype "passive"))
      (node (ref "U4") (pin "16") (pinfunction "VDD3.3_16") (pintype "power_in"))
      (node (ref "U4") (pin "25") (pinfunction "VDD3.3_25") (pintype "power_in"))
      (node (ref "U4") (pin "30") (pinfunction "VDD3.3_30") (pintype "power_in"))
      (node (ref "U4") (pin "31") (pinfunction "REG_EN_31") (pintype "passive"))
      (node (ref "U4") (pin "6") (pinfunction "VDD3.3_6") (pintype "power_in"))
    )
    (net (code "70") (name "5V") (class "Default")
      (node (ref "C20") (pin "2") (pinfunction "2_2") (pintype "passive"))
      (node (ref "C21") (pin "1") (pinfunction "1_1") (pintype "passive"))
      (node (ref "C24") (pin "1") (pinfunction "1_1") (pintype "passive"))
      (node (ref "C25") (pin "1") (pinfunction "1_1") (pintype "passive"))
      (node (ref "C7") (pin "2") (pinfunction "2_2") (pintype "passive"))
      (node (ref "D5") (pin "2") (pinfunction "K_2") (pintype "passive"))
      (node (ref "L2") (pin "1") (pinfunction "1_1") (pintype "passive"))
      (node (ref "P1") (pin "1") (pinfunction "1_1") (pintype "passive"))
      (node (ref "P2") (pin "1") (pinfunction "1_1") (pintype "passive"))
      (node (ref "U2") (pin "1") (pinfunction "IN_1") (pintype "passive"))
      (node (ref "U3") (pin "1") (pinfunction "VIN_1") (pintype "passive"))
      (node (ref "U3") (pin "3") (pinfunction "CE_3") (pintype "passive"))
      (node (ref "U4") (pin "4") (pinfunction "VBUS_4") (pintype "power_in"))
    )
    (net (code "71") (name "GND") (class "Default")
      (node (ref "C1") (pin "1") (pinfunction "1_1") (pintype "passive"))
      (node (ref "C10") (pin "1") (pinfunction "1_1") (pintype "passive"))
      (node (ref "C11") (pin "1") (pinfunction "1_1") (pintype "passive"))
      (node (ref "C12") (pin "1") (pinfunction "1_1") (pintype "passive"))
      (node (ref "C13") (pin "1") (pinfunction "1_1") (pintype "passive"))
      (node (ref "C14") (pin "1") (pinfunction "1_1") (pintype "passive"))
      (node (ref "C15") (pin "1") (pinfunction "1_1") (pintype "passive"))
      (node (ref "C16") (pin "1") (pinfunction "1_1") (pintype "passive"))
      (node (ref "C17") (pin "1") (pinfunction "1_1") (pintype "passive"))
      (node (ref "C18") (pin "1") (pinfunction "1_1") (pintype "passive"))
      (node (ref "C19") (pin "1") (pinfunction "1_1") (pintype "passive"))
      (node (ref "C2") (pin "1") (pinfunction "1_1") (pintype "passive"))
      (node (ref "C20") (pin "1") (pinfunction "1_1") (pintype "passive"))
      (node (ref "C21") (pin "2") (pinfunction "2_2") (pintype "passive"))
      (node (ref "C22") (pin "1") (pinfunction "1_1") (pintype "passive"))
      (node (ref "C23") (pin "1") (pinfunction "1_1") (pintype "passive"))
      (node (ref "C24") (pin "2") (pinfunction "2_2") (pintype "passive"))
      (node (ref "C25") (pin "2") (pinfunction "2_2") (pintype "passive"))
      (node (ref "C26") (pin "2") (pinfunction "2_2") (pintype "passive"))
      (node (ref "C28") (pin "1") (pinfunction "1_1") (pintype "passive"))
      (node (ref "C29") (pin "1") (pinfunction "1_1") (pintype "passive"))
      (node (ref "C3") (pin "1") (pinfunction "1_1") (pintype "passive"))
      (node (ref "C30") (pin "1") (pinfunction "1_1") (pintype "passive"))
      (node (ref "C31") (pin "1") (pinfunction "1_1") (pintype "passive"))
      (node (ref "C32") (pin "1") (pinfunction "1_1") (pintype "passive"))
      (node (ref "C33") (pin "1") (pinfunction "1_1") (pintype "passive"))
      (node (ref "C34") (pin "1") (pinfunction "1_1") (pintype "passive"))
      (node (ref "C35") (pin "1") (pinfunction "1_1") (pintype "passive"))
      (node (ref "C36") (pin "1") (pinfunction "1_1") (pintype "passive"))
      (node (ref "C4") (pin "1") (pinfunction "1_1") (pintype "passive"))
      (node (ref "C5") (pin "1") (pinfunction "1_1") (pintype "passive"))
      (node (ref "C6") (pin "1") (pinfunction "1_1") (pintype "passive"))
      (node (ref "C7") (pin "1") (pinfunction "1_1") (pintype "passive"))
      (node (ref "C8") (pin "1") (pinfunction "1_1") (pintype "passive"))
      (node (ref "C9") (pin "1") (pinfunction "1_1") (pintype "passive"))
      (node (ref "D10") (pin "1") (pinfunction "A_1") (pintype "passive"))
      (node (ref "D11") (pin "1") (pinfunction "A_1") (pintype "passive"))
      (node (ref "D12") (pin "1") (pinfunction "A_1") (pintype "passive"))
      (node (ref "D13") (pin "1") (pinfunction "A_1") (pintype "passive"))
      (node (ref "D14") (pin "1") (pinfunction "A_1") (pintype "passive"))
      (node (ref "D15") (pin "1") (pinfunction "A_1") (pintype "passive"))
      (node (ref "D16") (pin "1") (pinfunction "A_1") (pintype "passive"))
      (node (ref "D17") (pin "1") (pinfunction "A_1") (pintype "passive"))
      (node (ref "D18") (pin "1") (pinfunction "A_1") (pintype "passive"))
      (node (ref "D19") (pin "1") (pinfunction "A_1") (pintype "passive"))
      (node (ref "D20") (pin "1") (pinfunction "A_1") (pintype "passive"))
      (node (ref "D21") (pin "1") (pinfunction "A_1") (pintype "passive"))
      (node (ref "D22") (pin "1") (pinfunction "A_1") (pintype "passive"))
      (node (ref "D23") (pin "1") (pinfunction "A_1") (pintype "passive"))
      (node (ref "D5") (pin "1") (pinfunction "A_1") (pintype "passive"))
      (node (ref "D6") (pin "1") (pinfunction "A_1") (pintype "passive"))
      (node (ref "D8") (pin "1") (pinfunction "A_1") (pintype "passive"))
      (node (ref "D9") (pin "1") (pinfunction "A_1") (pintype "passive"))
      (node (ref "J2") (pin "A1") (pinfunction "GND_A1") (pintype "passive"))
      (node (ref "J2") (pin "A12") (pinfunction "GND_A12") (pintype "passive"))
      (node (ref "J2") (pin "B1") (pinfunction "GND_B1") (pintype "passive"))
      (node (ref "J2") (pin "B12") (pinfunction "GND_B12") (pintype "passive"))
      (node (ref "P1") (pin "11") (pinfunction "11_11") (pintype "passive"))
      (node (ref "P2") (pin "11") (pinfunction "11_11") (pintype "passive"))
      (node (ref "P3") (pin "1") (pinfunction "1_1") (pintype "passive"))
      (node (ref "P3") (pin "17") (pinfunction "17_17") (pintype "passive"))
      (node (ref "P3") (pin "19") (pinfunction "19_19") (pintype "passive"))
      (node (ref "P3") (pin "3") (pinfunction "3_3") (pintype "passive"))
      (node (ref "R2") (pin "1") (pinfunction "1_1") (pintype "passive"))
      (node (ref "R3") (pin "1") (pinfunction "1_1") (pintype "passive"))
      (node (ref "R6") (pin "1") (pinfunction "1_1") (pintype "passive"))
      (node (ref "R9") (pin "1") (pinfunction "1_1") (pintype "passive"))
      (node (ref "T4") (pin "1") (pintype "power_in"))
      (node (ref "U1") (pin "10") (pinfunction "VSS_10") (pintype "power_in"))
      (node (ref "U1") (pin "20") (pinfunction "VSSA_20") (pintype "power_in"))
      (node (ref "U1") (pin "27") (pinfunction "VSS_27") (pintype "power_in"))
      (node (ref "U1") (pin "74") (pinfunction "VSS_74") (pintype "power_in"))
      (node (ref "U1") (pin "99") (pinfunction "VSS_99") (pintype "power_in"))
      (node (ref "U2") (pin "3") (pinfunction "GND_3") (pintype "passive"))
      (node (ref "U3") (pin "2") (pinfunction "VSS_2") (pintype "passive"))
      (node (ref "U4") (pin "0") (pinfunction "GND_FLAG_0") (pintype "power_in"))
      (node (ref "U4") (pin "1") (pinfunction "GND_1") (pintype "power_in"))
      (node (ref "U4") (pin "2") (pinfunction "GND_2") (pintype "power_in"))
    )
    (net (code "72") (name "Net-(C26-Pad1)") (class "Default")
      (node (ref "C26") (pin "1") (pinfunction "1_1") (pintype "passive"))
      (node (ref "J2") (pin "SHELL") (pinfunction "SHELL_SHELL") (pintype "passive"))
      (node (ref "R9") (pin "2") (pinfunction "2_2") (pintype "passive"))
    )
    (net (code "73") (name "Net-(C34-Pad2)") (class "Default")
      (node (ref "C34") (pin "2") (pinfunction "2_2") (pintype "passive"))
      (node (ref "U4") (pin "15") (pinfunction "VDD1.8_15") (pintype "power_in"))
    )
    (net (code "74") (name "Net-(C35-Pad2)") (class "Default")
      (node (ref "C35") (pin "2") (pinfunction "2_2") (pintype "passive"))
      (node (ref "U4") (pin "26") (pinfunction "VDD1.8_26") (pintype "power_in"))
    )
    (net (code "75") (name "Net-(F1-Pad1)") (class "Default")
      (node (ref "F1") (pin "1") (pinfunction "1_1") (pintype "passive"))
      (node (ref "L2") (pin "2") (pinfunction "2_2") (pintype "passive"))
    )
    (net (code "76") (name "Net-(F1-Pad2)") (class "Default")
      (node (ref "F1") (pin "2") (pinfunction "2_2") (pintype "passive"))
      (node (ref "J2") (pin "A4") (pinfunction "VBUS_A4") (pintype "passive"))
      (node (ref "J2") (pin "A9") (pinfunction "VBUS_A9") (pintype "passive"))
      (node (ref "J2") (pin "B4") (pinfunction "VBUS_B4") (pintype "passive"))
      (node (ref "J2") (pin "B9") (pinfunction "VBUS_B9") (pintype "passive"))
    )
    (net (code "77") (name "Net-(U1D-BOOT0{slash}VPP)") (class "Default")
      (node (ref "R2") (pin "2") (pinfunction "2_2") (pintype "passive"))
      (node (ref "U1") (pin "94") (pinfunction "BOOT0/VPP_94") (pintype "input"))
    )
    (net (code "78") (name "Net-(U1D-NRST)") (class "Default")
      (node (ref "C3") (pin "2") (pinfunction "2_2") (pintype "passive"))
      (node (ref "R1") (pin "1") (pinfunction "1_1") (pintype "passive"))
      (node (ref "U1") (pin "14") (pinfunction "NRST_14") (pintype "bidirectional"))
    )
    (net (code "79") (name "Net-(U1D-PH0-OSC_IN(PH0){slash}EVENTOUT{slash}OSC_IN)") (class "Default")
      (node (ref "C2") (pin "2") (pinfunction "2_2") (pintype "passive"))
      (node (ref "U1") (pin "12") (pinfunction "PH0-OSC_IN(PH0)/EVENTOUT/OSC_IN_12") (pintype "bidirectional"))
      (node (ref "XT1") (pin "2") (pinfunction "2_2") (pintype "passive"))
    )
    (net (code "80") (name "Net-(U1D-PH1-OSC_OUT(PH1){slash}EVENTOUT{slash}OSC_OUT)") (class "Default")
      (node (ref "C1") (pin "2") (pinfunction "2_2") (pintype "passive"))
      (node (ref "U1") (pin "13") (pinfunction "PH1-OSC_OUT(PH1)/EVENTOUT/OSC_OUT_13") (pintype "bidirectional"))
      (node (ref "XT1") (pin "1") (pinfunction "1_1") (pintype "passive"))
    )
    (net (code "81") (name "Net-(U1D-VCAP_1)") (class "Default")
      (node (ref "C4") (pin "2") (pinfunction "2_2") (pintype "passive"))
      (node (ref "U1") (pin "49") (pinfunction "VCAP_1_49") (pintype "power_in"))
    )
    (net (code "82") (name "Net-(U1D-VCAP_2)") (class "Default")
      (node (ref "C5") (pin "2") (pinfunction "2_2") (pintype "passive"))
      (node (ref "U1") (pin "73") (pinfunction "VCAP_2_73") (pintype "power_in"))
    )
    (net (code "83") (name "Net-(U1E-VDDA)") (class "Default")
      (node (ref "C18") (pin "2") (pinfunction "2_2") (pintype "passive"))
      (node (ref "C19") (pin "2") (pinfunction "2_2") (pintype "passive"))
      (node (ref "L1") (pin "2") (pinfunction "2_2") (pintype "passive"))
      (node (ref "U1") (pin "22") (pinfunction "VDDA_22") (pintype "power_in"))
    )
    (net (code "84") (name "Net-(U1E-VREF+)") (class "Default")
      (node (ref "C6") (pin "2") (pinfunction "2_2") (pintype "passive"))
      (node (ref "U1") (pin "21") (pinfunction "VREF+_21") (pintype "power_in"))
      (node (ref "U2") (pin "2") (pinfunction "OUT_2") (pintype "passive"))
    )
    (net (code "85") (name "Net-(U4-RBIAS)") (class "Default")
      (node (ref "R6") (pin "2") (pinfunction "2_2") (pintype "passive"))
      (node (ref "U4") (pin "32") (pinfunction "RBIAS_32") (pintype "passive"))
    )
    (net (code "86") (name "Net-(U4-RESET)") (class "Default")
      (node (ref "C27") (pin "1") (pinfunction "1_1") (pintype "passive"))
      (node (ref "R3") (pin "2") (pinfunction "2_2") (pintype "passive"))
      (node (ref "U4") (pin "9") (pinfunction "RESET_9") (pintype "input"))
    )
    (net (code "87") (name "Net-(U4-VDDA1.8)") (class "Default")
      (node (ref "C36") (pin "2") (pinfunction "2_2") (pintype "passive"))
      (node (ref "U4") (pin "29") (pinfunction "VDDA1.8_29") (pintype "power_in"))
    )
    (net (code "88") (name "Net-(U4-XI)") (class "Default")
      (node (ref "C33") (pin "2") (pinfunction "2_2") (pintype "passive"))
      (node (ref "R4") (pin "2") (pinfunction "2_2") (pintype "passive"))
      (node (ref "U4") (pin "28") (pinfunction "XI_28") (pintype "passive"))
      (node (ref "XT2") (pin "2") (pinfunction "2_2") (pintype "passive"))
    )
    (net (code "89") (name "Net-(U4-XO)") (class "Default")
      (node (ref "C32") (pin "2") (pinfunction "2_2") (pintype "passive"))
      (node (ref "R4") (pin "1") (pinfunction "1_1") (pintype "passive"))
      (node (ref "U4") (pin "27") (pinfunction "XO_27") (pintype "passive"))
      (node (ref "XT2") (pin "1") (pinfunction "1_1") (pintype "passive"))
    )
    (net (code "90") (name "unconnected-(J2-CC1-PadA5)") (class "Default")
      (node (ref "J2") (pin "A5") (pinfunction "CC1_A5") (pintype "passive"))
    )
    (net (code "91") (name "unconnected-(J2-CC2-PadB5)") (class "Default")
      (node (ref "J2") (pin "B5") (pinfunction "CC2_B5") (pintype "passive"))
    )
    (net (code "92") (name "unconnected-(J2-SBU1-PadA8)") (class "Default")
      (node (ref "J2") (pin "A8") (pinfunction "SBU1_A8") (pintype "passive"))
    )
    (net (code "93") (name "unconnected-(J2-SBU2-PadB8)") (class "Default")
      (node (ref "J2") (pin "B8") (pinfunction "SBU2_B8") (pintype "passive"))
    )
    (net (code "94") (name "unconnected-(U1A-PA2{slash}USART2_TX{slash}TIM5_CH3{slash}TIM9_CH1{slash}TIM2_CH3{slash}ETH_MDIO{slash}EVENTOUT{slash}ADC123_IN2-Pad25)") (class "Default")
      (node (ref "U1") (pin "25") (pinfunction "PA2/USART2_TX/TIM5_CH3/TIM9_CH1/TIM2_CH3/ETH_MDIO/EVENTOUT/ADC123_IN2_25") (pintype "bidirectional"))
    )
    (net (code "95") (name "unconnected-(U1A-PA9{slash}USART1_TX{slash}TIM1_CH2{slash}I2C3_SMBA{slash}DCMI_D0{slash}EVENTOUT{slash}OTG_FS_VBUS-Pad68)") (class "Default")
      (node (ref "U1") (pin "68") (pinfunction "PA9/USART1_TX/TIM1_CH2/I2C3_SMBA/DCMI_D0/EVENTOUT/OTG_FS_VBUS_68") (pintype "bidirectional"))
    )
    (net (code "96") (name "unconnected-(U1A-PA10{slash}USART1_RX{slash}TIM1_CH3{slash}OTG_FS_ID{slash}DCMI_D1{slash}EVENTOUT-Pad69)") (class "Default")
      (node (ref "U1") (pin "69") (pinfunction "PA10/USART1_RX/TIM1_CH3/OTG_FS_ID/DCMI_D1/EVENTOUT_69") (pintype "bidirectional"))
    )
    (net (code "97") (name "unconnected-(U1A-PA11{slash}USART1_CTS{slash}CAN1_RX{slash}TIM1_CH4{slash}OTG_FS_DM{slash}EVENTOUT-Pad70)") (class "Default")
      (node (ref "U1") (pin "70") (pinfunction "PA11/USART1_CTS/CAN1_RX/TIM1_CH4/OTG_FS_DM/EVENTOUT_70") (pintype "bidirectional"))
    )
    (net (code "98") (name "unconnected-(U1A-PA12{slash}USART1_RTS{slash}CAN1_TX{slash}TIM1_ETR{slash}OTG_FS_DP{slash}EVENTOUT-Pad71)") (class "Default")
      (node (ref "U1") (pin "71") (pinfunction "PA12/USART1_RTS/CAN1_TX/TIM1_ETR/OTG_FS_DP/EVENTOUT_71") (pintype "bidirectional"))
    )
    (net (code "99") (name "unconnected-(U1A-PB2-BOOT1(PB2){slash}EVENTOUT-Pad37)") (class "Default")
      (node (ref "U1") (pin "37") (pinfunction "PB2-BOOT1(PB2)/EVENTOUT_37") (pintype "bidirectional"))
    )
    (net (code "100") (name "unconnected-(U1A-PB4(NJTRST){slash}NJTRST{slash}SPI3_MISO{slash}TIM3_CH1{slash}SPI1_MISO{slash}I2S3ext_SD{slash}EVENTOUT-Pad90)") (class "Default")
      (node (ref "U1") (pin "90") (pinfunction "PB4(NJTRST)/NJTRST/SPI3_MISO/TIM3_CH1/SPI1_MISO/I2S3ext_SD/EVENTOUT_90") (pintype "bidirectional"))
    )
    (net (code "101") (name "unconnected-(U1B-PC1{slash}ETH_MDC{slash}EVENTOUT{slash}ADC123_IN11-Pad16)") (class "Default")
      (node (ref "U1") (pin "16") (pinfunction "PC1/ETH_MDC/EVENTOUT/ADC123_IN11_16") (pintype "bidirectional"))
    )
    (net (code "102") (name "unconnected-(U1B-PC4{slash}ETH_RMII_RX_D0{slash}ETH_MII_RX_D0{slash}EVENTOUT{slash}ADC12_IN14-Pad33)") (class "Default")
      (node (ref "U1") (pin "33") (pinfunction "PC4/ETH_RMII_RX_D0/ETH_MII_RX_D0/EVENTOUT/ADC12_IN14_33") (pintype "bidirectional"))
    )
    (net (code "103") (name "unconnected-(U1B-PC5{slash}ETH_RMII_RX_D1{slash}ETH_MII_RX_D1{slash}EVENTOUT{slash}ADC12_IN15-Pad34)") (class "Default")
      (node (ref "U1") (pin "34") (pinfunction "PC5/ETH_RMII_RX_D1/ETH_MII_RX_D1/EVENTOUT/ADC12_IN15_34") (pintype "bidirectional"))
    )
    (net (code "104") (name "unconnected-(U1B-PC6{slash}I2S2_MCK{slash}TIM8_CH1{slash}SDIO_D6{slash}USART6_TX{slash}DCMI_D0{slash}TIM3_CH1{slash}EVENTOUT-Pad63)") (class "Default")
      (node (ref "U1") (pin "63") (pinfunction "PC6/I2S2_MCK/TIM8_CH1/SDIO_D6/USART6_TX/DCMI_D0/TIM3_CH1/EVENTOUT_63") (pintype "bidirectional"))
    )
    (net (code "105") (name "unconnected-(U1B-PC7{slash}I2S3_MCK{slash}TIM8_CH2{slash}SDIO_D7{slash}USART6_RX{slash}DCMI_D1{slash}TIM3_CH2{slash}EVENTOUT-Pad64)") (class "Default")
      (node (ref "U1") (pin "64") (pinfunction "PC7/I2S3_MCK/TIM8_CH2/SDIO_D7/USART6_RX/DCMI_D1/TIM3_CH2/EVENTOUT_64") (pintype "bidirectional"))
    )
    (net (code "106") (name "unconnected-(U1B-PC8{slash}TIM8_CH3{slash}SDIO_D0{slash}TIM3_CH3{slash}USART6_CK{slash}DCMI_D2{slash}EVENTOUT-Pad65)") (class "Default")
      (node (ref "U1") (pin "65") (pinfunction "PC8/TIM8_CH3/SDIO_D0/TIM3_CH3/USART6_CK/DCMI_D2/EVENTOUT_65") (pintype "bidirectional"))
    )
    (net (code "107") (name "unconnected-(U1B-PC13{slash}EVENTOUT{slash}RTC_AF1-Pad7)") (class "Default")
      (node (ref "U1") (pin "7") (pinfunction "PC13/EVENTOUT/RTC_AF1_7") (pintype "bidirectional"))
    )
    (net (code "108") (name "unconnected-(U1B-PC14-OSC32_IN(PC14){slash}EVENTOUT{slash}OSC32_IN-Pad8)") (class "Default")
      (node (ref "U1") (pin "8") (pinfunction "PC14-OSC32_IN(PC14)/EVENTOUT/OSC32_IN_8") (pintype "bidirectional"))
    )
    (net (code "109") (name "unconnected-(U1B-PC15-OSC32_OUT(PC15){slash}EVENTOUT{slash}OSC32_OUT-Pad9)") (class "Default")
      (node (ref "U1") (pin "9") (pinfunction "PC15-OSC32_OUT(PC15)/EVENTOUT/OSC32_OUT_9") (pintype "bidirectional"))
    )
    (net (code "110") (name "unconnected-(U1B-PD2{slash}TIM3_ETR{slash}UART5_RX{slash}SDIO_CMD{slash}DCMI_D11{slash}EVENTOUT-Pad83)") (class "Default")
      (node (ref "U1") (pin "83") (pinfunction "PD2/TIM3_ETR/UART5_RX/SDIO_CMD/DCMI_D11/EVENTOUT_83") (pintype "bidirectional"))
    )
    (net (code "111") (name "unconnected-(U1B-PD3{slash}FSMC_CLK{slash}USART2_CTS{slash}EVENTOUT-Pad84)") (class "Default")
      (node (ref "U1") (pin "84") (pinfunction "PD3/FSMC_CLK/USART2_CTS/EVENTOUT_84") (pintype "bidirectional"))
    )
    (net (code "112") (name "unconnected-(U1B-PD9{slash}FSMC_D14{slash}USART3_RX{slash}EVENTOUT-Pad56)") (class "Default")
      (node (ref "U1") (pin "56") (pinfunction "PD9/FSMC_D14/USART3_RX/EVENTOUT_56") (pintype "bidirectional"))
    )
    (net (code "113") (name "unconnected-(U1B-PD10{slash}FSMC_D15{slash}USART3_CK{slash}EVENTOUT-Pad57)") (class "Default")
      (node (ref "U1") (pin "57") (pinfunction "PD10/FSMC_D15/USART3_CK/EVENTOUT_57") (pintype "bidirectional"))
    )
    (net (code "114") (name "unconnected-(U1B-PD13{slash}FSMC_A18{slash}TIM4_CH2{slash}EVENTOUT-Pad60)") (class "Default")
      (node (ref "U1") (pin "60") (pinfunction "PD13/FSMC_A18/TIM4_CH2/EVENTOUT_60") (pintype "bidirectional"))
    )
    (net (code "115") (name "unconnected-(U1C-PE0{slash}TIM4_ETR{slash}FSMC_NBL0{slash}DCMI_D2{slash}EVENTOUT-Pad97)") (class "Default")
      (node (ref "U1") (pin "97") (pinfunction "PE0/TIM4_ETR/FSMC_NBL0/DCMI_D2/EVENTOUT_97") (pintype "bidirectional"))
    )
    (net (code "116") (name "unconnected-(U1C-PE1{slash}FSMC_NBL1{slash}DCMI_D3{slash}EVENTOUT-Pad98)") (class "Default")
      (node (ref "U1") (pin "98") (pinfunction "PE1/FSMC_NBL1/DCMI_D3/EVENTOUT_98") (pintype "bidirectional"))
    )
    (net (code "117") (name "unconnected-(U1C-PE2{slash}TRACECLK{slash}FSMC_A23{slash}ETH_MII_TXD3{slash}EVENTOUT-Pad1)") (class "Default")
      (node (ref "U1") (pin "1") (pinfunction "PE2/TRACECLK/FSMC_A23/ETH_MII_TXD3/EVENTOUT_1") (pintype "bidirectional"))
    )
    (net (code "118") (name "unconnected-(U1C-PE3{slash}TRACED0{slash}FSMC_A19{slash}EVENTOUT-Pad2)") (class "Default")
      (node (ref "U1") (pin "2") (pinfunction "PE3/TRACED0/FSMC_A19/EVENTOUT_2") (pintype "bidirectional"))
    )
    (net (code "119") (name "unconnected-(U1C-PE4{slash}TRACED1{slash}FSMC_A20{slash}DCMI_D4{slash}EVENTOUT-Pad3)") (class "Default")
      (node (ref "U1") (pin "3") (pinfunction "PE4/TRACED1/FSMC_A20/DCMI_D4/EVENTOUT_3") (pintype "bidirectional"))
    )
    (net (code "120") (name "unconnected-(U1C-PE5{slash}TRACED2{slash}FSMC_A21{slash}TIM9_CH1{slash}DCMI_D6{slash}EVENTOUT-Pad4)") (class "Default")
      (node (ref "U1") (pin "4") (pinfunction "PE5/TRACED2/FSMC_A21/TIM9_CH1/DCMI_D6/EVENTOUT_4") (pintype "bidirectional"))
    )
    (net (code "121") (name "unconnected-(U1C-PE6{slash}TRACED3{slash}FSMC_A22{slash}TIM9_CH2{slash}DCMI_D7{slash}EVENTOUT-Pad5)") (class "Default")
      (node (ref "U1") (pin "5") (pinfunction "PE6/TRACED3/FSMC_A22/TIM9_CH2/DCMI_D7/EVENTOUT_5") (pintype "bidirectional"))
    )
    (net (code "122") (name "unconnected-(U1C-PE11{slash}FSMC_D8{slash}TIM1_CH2{slash}EVENTOUT-Pad42)") (class "Default")
      (node (ref "U1") (pin "42") (pinfunction "PE11/FSMC_D8/TIM1_CH2/EVENTOUT_42") (pintype "bidirectional"))
    )
    (net (code "123") (name "unconnected-(U1C-PE12{slash}FSMC_D9{slash}TIM1_CH3N{slash}EVENTOUT-Pad43)") (class "Default")
      (node (ref "U1") (pin "43") (pinfunction "PE12/FSMC_D9/TIM1_CH3N/EVENTOUT_43") (pintype "bidirectional"))
    )
    (net (code "124") (name "unconnected-(U1C-PE13{slash}FSMC_D10{slash}TIM1_CH3{slash}EVENTOUT-Pad44)") (class "Default")
      (node (ref "U1") (pin "44") (pinfunction "PE13/FSMC_D10/TIM1_CH3/EVENTOUT_44") (pintype "bidirectional"))
    )
    (net (code "125") (name "unconnected-(U1C-PE14{slash}FSMC_D11{slash}TIM1_CH4{slash}EVENTOUT-Pad45)") (class "Default")
      (node (ref "U1") (pin "45") (pinfunction "PE14/FSMC_D11/TIM1_CH4/EVENTOUT_45") (pintype "bidirectional"))
    )
    (net (code "126") (name "unconnected-(U1C-PE15{slash}FSMC_D12{slash}TIM1_BKIN{slash}EVENTOUT-Pad46)") (class "Default")
      (node (ref "U1") (pin "46") (pinfunction "PE15/FSMC_D12/TIM1_BKIN/EVENTOUT_46") (pintype "bidirectional"))
    )
    (net (code "127") (name "unconnected-(U3-NC-Pad4)") (class "Default")
      (node (ref "U3") (pin "4") (pinfunction "NC_4") (pintype "passive"))
    )
    (net (code "128") (name "unconnected-(U4-CPEN-Pad3)") (class "Default")
      (node (ref "U4") (pin "3") (pinfunction "CPEN_3") (pintype "power_in"))
    )
    (net (code "129") (name "unconnected-(U4-EXTVBUS-Pad10)") (class "Default")
      (node (ref "U4") (pin "10") (pinfunction "EXTVBUS_10") (pintype "passive"))
    )
    (net (code "130") (name "unconnected-(U4-ID-Pad5)") (class "Default")
      (node (ref "U4") (pin "5") (pinfunction "ID_5") (pintype "passive"))
    )
  )
)
